# 555_Astable.net
KiCad netlist of a schematic drawn in EAGLE
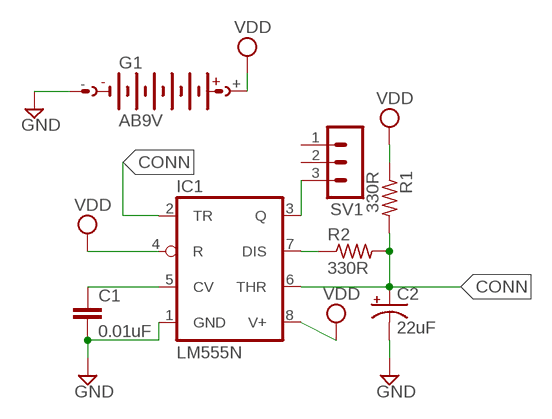
[diagram p0: schematic, sheet 1]

(export (version "E")
  (design (tool "Eeschema 10.0.6"))
  (components
    (comp (ref "C1")
      (value "0.01uF")
      (footprint "eagle-import:C5B2.5")
      (libsource (lib "eagle-import") (part "C5/2.5"))
    )
    (comp (ref "C2")
      (value "22uF")
      (footprint "eagle-import:E3,5-8")
      (libsource (lib "eagle-import") (part "CPOL-USE3.5-8"))
    )
    (comp (ref "G1")
      (value "AB9V")
      (footprint "eagle-import:AB9V")
      (libsource (lib "eagle-import") (part "AB9V"))
    )
    (comp (ref "IC1")
      (value "LM555N")
      (footprint "eagle-import:DIL08")
      (libsource (lib "eagle-import") (part "555NLM"))
    )
    (comp (ref "R1")
      (value "330R")
      (footprint "eagle-import:0207_10")
      (libsource (lib "eagle-import") (part "R-US_0207/10"))
    )
    (comp (ref "R2")
      (value "330R")
      (footprint "eagle-import:0207_10")
      (libsource (lib "eagle-import") (part "R-US_0207/10"))
    )
    (comp (ref "SV1")
      (value "MA03-1")
      (footprint "eagle-import:MA03-1")
      (libsource (lib "eagle-import") (part "MA03-1"))
    )
  )
  (nets
    (net (code "1") (name "CONN") (class "Default")
      (node (ref "C2") (pin "+") (pinfunction "+_+") (pintype "passive"))
      (node (ref "IC1") (pin "2") (pinfunction "TR_2") (pintype "input"))
      (node (ref "IC1") (pin "6") (pinfunction "THR_6") (pintype "input"))
      (node (ref "R1") (pin "2") (pinfunction "2_2") (pintype "passive"))
      (node (ref "R2") (pin "2") (pinfunction "2_2") (pintype "passive"))
    )
    (net (code "2") (name "GND") (class "Default")
      (node (ref "C1") (pin "2") (pinfunction "2_2") (pintype "passive"))
      (node (ref "C2") (pin "-") (pinfunction "-_-") (pintype "passive"))
      (node (ref "G1") (pin "-") (pinfunction "-_-") (pintype "passive"))
      (node (ref "IC1") (pin "1") (pinfunction "GND_1") (pintype "power_in"))
    )
    (net (code "3") (name "Net-(IC1-CV)") (class "Default")
      (node (ref "C1") (pin "1") (pinfunction "1_1") (pintype "passive"))
      (node (ref "IC1") (pin "5") (pinfunction "CV_5") (pintype "input"))
    )
    (net (code "4") (name "Net-(IC1-DIS)") (class "Default")
      (node (ref "IC1") (pin "7") (pinfunction "DIS_7") (pintype "input"))
      (node (ref "R2") (pin "1") (pinfunction "1_1") (pintype "passive"))
    )
    (net (code "5") (name "Net-(IC1-Q)") (class "Default")
      (node (ref "IC1") (pin "3") (pinfunction "Q_3") (pintype "output"))
      (node (ref "SV1") (pin "3") (pinfunction "3_3") (pintype "passive"))
    )
    (net (code "6") (name "VDD") (class "Default")
      (node (ref "G1") (pin "+") (pinfunction "+_+") (pintype "passive"))
      (node (ref "IC1") (pin "4") (pinfunction "R_4") (pintype "input"))
      (node (ref "IC1") (pin "8") (pinfunction "V+_8") (pintype "power_in"))
      (node (ref "R1") (pin "1") (pinfunction "1_1") (pintype "passive"))
    )
    (net (code "7") (name "unconnected-(SV1-Pad1)") (class "Default")
      (node (ref "SV1") (pin "1") (pinfunction "1_1") (pintype "passive"))
    )
    (net (code "8") (name "unconnected-(SV1-Pad2)") (class "Default")
      (node (ref "SV1") (pin "2") (pinfunction "2_2") (pintype "passive"))
    )
  )
)
